# lm1117-5.net
KiCad netlist of a schematic drawn in Altium Designer
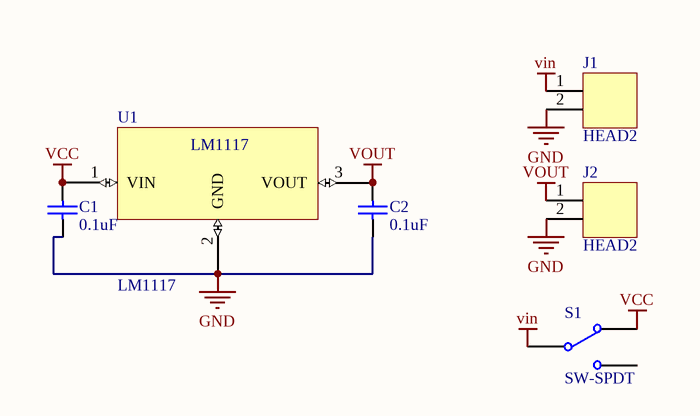
[diagram p0: lm1117-5.SchDoc]

(export (version "E")
  (design (tool "Eeschema 10.0.6"))
  (components
    (comp (ref "C1")
      (value "0.1uF")
      (footprint "CC1005-0402")
      (description "Capacitor")
      (fields
        (field (name "MANUFACTURER") "Generic Components")
        (field (name "Comment") "CAP")
        (field (name "PUBLISHER") "Altium Hobart Technology Centre")
      )
      (libsource (lib "HGH") (part "CAP"))
    )
    (comp (ref "C2")
      (value "0.1uF")
      (footprint "CC1005-0402")
      (description "Capacitor")
      (fields
        (field (name "MANUFACTURER") "Generic Components")
        (field (name "Comment") "CAP")
        (field (name "PUBLISHER") "Altium Hobart Technology Centre")
      )
      (libsource (lib "HGH") (part "CAP"))
    )
    (comp (ref "J1")
      (value "HEAD2")
      (footprint "HEAD2M")
      (description "Connector,2-pin")
      (libsource (lib "HGH") (part "HEAD2"))
    )
    (comp (ref "J2")
      (value "HEAD2")
      (footprint "HEAD2M")
      (description "Connector,2-pin")
      (libsource (lib "HGH") (part "HEAD2"))
    )
    (comp (ref "S1")
      (value "SW-SPDT")
      (footprint "SPDT-3Z")
      (description "Single-Pole, Double-Throw Switch")
      (fields (field (name "MANUFACTURER") "Generic Components"))
      (libsource (lib "HGH") (part "SW-SPDT"))
    )
    (comp (ref "U1") (value "LM1117") (footprint "DSO-G3/P2.3") (libsource (lib "HGH") (part "LM1117")))
  )
  (nets
    (net (code "1") (name "GND") (class "Default")
      (node (ref "C1") (pin "1") (pinfunction "1_1") (pintype "passive"))
      (node (ref "C2") (pin "1") (pinfunction "1_1") (pintype "passive"))
      (node (ref "J1") (pin "2") (pinfunction "2_2") (pintype "passive"))
      (node (ref "J2") (pin "2") (pinfunction "2_2") (pintype "passive"))
      (node (ref "U1") (pin "2") (pinfunction "GND_2") (pintype "bidirectional"))
    )
    (net (code "2") (name "VCC") (class "Default")
      (node (ref "C1") (pin "2") (pinfunction "2_2") (pintype "passive"))
      (node (ref "S1") (pin "1") (pinfunction "NC_1") (pintype "passive"))
      (node (ref "U1") (pin "1") (pinfunction "VIN_1") (pintype "bidirectional"))
    )
    (net (code "3") (name "VOUT") (class "Default")
      (node (ref "C2") (pin "2") (pinfunction "2_2") (pintype "passive"))
      (node (ref "J2") (pin "1") (pinfunction "1_1") (pintype "passive"))
      (node (ref "U1") (pin "3") (pinfunction "VOUT_3") (pintype "bidirectional"))
    )
    (net (code "4") (name "unconnected-(S1-NO-Pad3)") (class "Default")
      (node (ref "S1") (pin "3") (pinfunction "NO_3") (pintype "passive"))
    )
    (net (code "5") (name "vin") (class "Default")
      (node (ref "J1") (pin "1") (pinfunction "1_1") (pintype "passive"))
      (node (ref "S1") (pin "2") (pinfunction "COMMON_2") (pintype "passive"))
    )
  )
)
